# bt_rc_car_remote.net
KiCad netlist of a schematic drawn in EAGLE
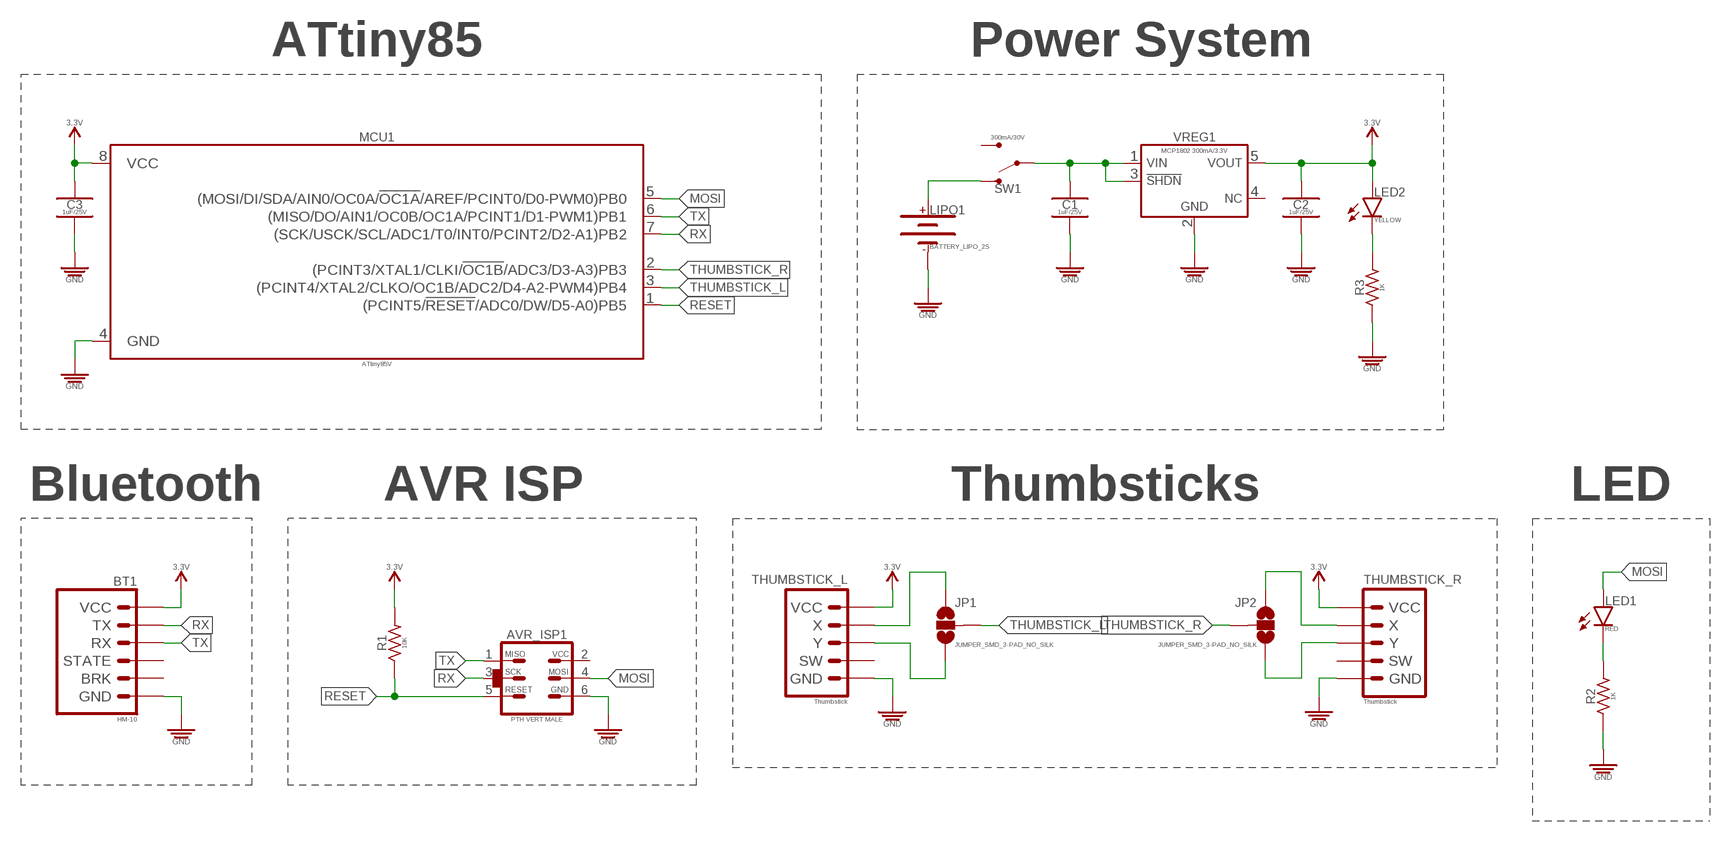
[diagram p0: schematic, sheet 1]

(export (version "E")
  (design (tool "Eeschema 10.0.6"))
  (components
    (comp (ref "AVR_ISP1")
      (value "PTH VERT MALE")
      (footprint "eagle-import:HDRV6W64P254_2X3_762X483X838B_AVR-ISP")
      (fields (field (name "MFR") "Amphenol FCI") (field (name "MPN") "67997-206HLF"))
      (libsource (lib "eagle-import") (part "AVR_SPI_PRG_6_PTH_VERT_MALE_2.54MM"))
    )
    (comp (ref "BT1")
      (value "HM-10")
      (footprint "eagle-import:HDRRAR6W60P254_1X6_1574X850X274B")
      (fields (field (name "MFR") "JNHuaMao Technology Company"))
      (libsource (lib "eagle-import") (part "BLUETOOTH_HM-10_PTH_RA_FEMALE_2.54MM"))
    )
    (comp (ref "C1")
      (value "1uF/25V")
      (footprint "eagle-import:CAPC2012X95_SMD-0805")
      (fields (field (name "MFR") "KEMET") (field (name "MPN") "C0805C105K3RACTU"))
      (libsource (lib "eagle-import") (part "1UF_CER_SMD-0805_25V-10%"))
    )
    (comp (ref "C2")
      (value "1uF/25V")
      (footprint "eagle-import:CAPC2012X95_SMD-0805")
      (fields (field (name "MFR") "KEMET") (field (name "MPN") "C0805C105K3RACTU"))
      (libsource (lib "eagle-import") (part "1UF_CER_SMD-0805_25V-10%"))
    )
    (comp (ref "C3")
      (value "1uF/25V")
      (footprint "eagle-import:CAPC2012X95_SMD-0805")
      (fields (field (name "MFR") "KEMET") (field (name "MPN") "C0805C105K3RACTU"))
      (libsource (lib "eagle-import") (part "1UF_CER_SMD-0805_25V-10%"))
    )
    (comp (ref "JP1")
      (value "JUMPER_SMD_3-PAD_NO_SILK")
      (footprint "eagle-import:SMT-JUMPER_3_NO_SILK")
      (libsource (lib "eagle-import") (part "JUMPER_SMD_3-PAD_NO_SILK"))
    )
    (comp (ref "JP2")
      (value "JUMPER_SMD_3-PAD_NO_SILK")
      (footprint "eagle-import:SMT-JUMPER_3_NO_SILK")
      (libsource (lib "eagle-import") (part "JUMPER_SMD_3-PAD_NO_SILK"))
    )
    (comp (ref "LED1")
      (value "RED")
      (footprint "eagle-import:LEDC2012X120_LED-0805")
      (fields (field (name "MFR") "Lite-On Inc.") (field (name "MPN") "LTST-C170KRKT"))
      (libsource (lib "eagle-import") (part "LED_SMD-0805_DISCRETE_RED"))
    )
    (comp (ref "LED2")
      (value "YELLOW")
      (footprint "eagle-import:LEDC2012X120_LED-0805")
      (fields (field (name "MFR") "Lite-On Inc.") (field (name "MPN") "LTST-C170KSKT"))
      (libsource (lib "eagle-import") (part "LED_SMD-0805_DISCRETE_YELLOW"))
    )
    (comp (ref "LIPO1")
      (value "BATTERY_LIPO_2S")
      (footprint "eagle-import:DUAL_PTH_PADS")
      (libsource (lib "eagle-import") (part "BATTERY_LIPO_2S"))
    )
    (comp (ref "MCU1")
      (value "ATtiny85V")
      (footprint "eagle-import:SOIC127P798X216-8")
      (fields (field (name "MFR") "Microchip Technology") (field (name "MPN") "ATTINY85V-10SU"))
      (libsource (lib "eagle-import") (part "ATTINY-X5_SO-8_ATTINY-85V"))
    )
    (comp (ref "R1")
      (value "10K")
      (footprint "eagle-import:RESC2012X60_SMD-0805")
      (fields (field (name "MFR") "Yageo") (field (name "MPN") "RC0805JR-0710KL"))
      (libsource (lib "eagle-import") (part "10KΩ_SMD-0805_1/8W-5%"))
    )
    (comp (ref "R2")
      (value "1K")
      (footprint "eagle-import:RESC2012X60_SMD-0805")
      (fields (field (name "MFR") "Yageo") (field (name "MPN") "RC0805JR-071KL"))
      (libsource (lib "eagle-import") (part "1KΩ_SMD-0805_1/8W-5%"))
    )
    (comp (ref "R3")
      (value "1K")
      (footprint "eagle-import:RESC2012X60_SMD-0805")
      (fields (field (name "MFR") "Yageo") (field (name "MPN") "RC0805JR-071KL"))
      (libsource (lib "eagle-import") (part "1KΩ_SMD-0805_1/8W-5%"))
    )
    (comp (ref "SW1")
      (value "300mA/30V")
      (footprint "eagle-import:SW_SLIDE_SPDT_VERT_8.6L-4.3W")
      (fields (field (name "MFR") "C&K") (field (name "MPN") "SS-12D07-VG 4 NS GA PA"))
      (libsource (lib "eagle-import") (part "SWITCH_SPDT_PTH_VERT_300MA-30V_8.6L-4.3W"))
    )
    (comp (ref "THUMBSTICK_L")
      (value "Thumbstick")
      (footprint "eagle-import:HDRRAR5W60P254_1X5_1320X850X274B")
      (fields (field (name "MFR") "WGCD"))
      (libsource (lib "eagle-import") (part "THUMBSTICK-2AXIS_BREAKOUT_PTH_RA_FEMALE_2.54MM"))
    )
    (comp (ref "THUMBSTICK_R")
      (value "Thumbstick")
      (footprint "eagle-import:HDRRAR5W60P254_1X5_1320X850X274B")
      (fields (field (name "MFR") "WGCD"))
      (libsource (lib "eagle-import") (part "THUMBSTICK-2AXIS_BREAKOUT_PTH_RA_FEMALE_2.54MM"))
    )
    (comp (ref "VREG1")
      (value "MCP1802 300mA/3.3V")
      (footprint "eagle-import:SOT95P280X145-5")
      (fields (field (name "MFR") "Microchip Technology") (field (name "MPN") "MCP1802T-3302I/OT"))
      (libsource (lib "eagle-import") (part "MCP18XX_MCP1802-330_300MA-3.3V"))
    )
  )
  (nets
    (net (code "1") (name "3.3V") (class "Default")
      (node (ref "BT1") (pin "VCC") (pinfunction "VCC_VCC") (pintype "passive"))
      (node (ref "C2") (pin "1") (pinfunction "1_1") (pintype "passive"))
      (node (ref "C3") (pin "1") (pinfunction "1_1") (pintype "passive"))
      (node (ref "LED2") (pin "A") (pinfunction "A_A") (pintype "passive"))
      (node (ref "MCU1") (pin "8") (pinfunction "VCC_8") (pintype "power_in"))
      (node (ref "R1") (pin "2") (pinfunction "2_2") (pintype "passive"))
      (node (ref "THUMBSTICK_L") (pin "VCC") (pinfunction "VCC_VCC") (pintype "passive"))
      (node (ref "THUMBSTICK_R") (pin "VCC") (pinfunction "VCC_VCC") (pintype "passive"))
      (node (ref "VREG1") (pin "5") (pinfunction "VOUT_5") (pintype "passive"))
    )
    (net (code "2") (name "GND") (class "Default")
      (node (ref "AVR_ISP1") (pin "GND") (pinfunction "GND_GND") (pintype "power_in"))
      (node (ref "BT1") (pin "GND") (pinfunction "GND_GND") (pintype "passive"))
      (node (ref "C1") (pin "2") (pinfunction "2_2") (pintype "passive"))
      (node (ref "C2") (pin "2") (pinfunction "2_2") (pintype "passive"))
      (node (ref "C3") (pin "2") (pinfunction "2_2") (pintype "passive"))
      (node (ref "LIPO1") (pin "-") (pinfunction "-_-") (pintype "power_in"))
      (node (ref "MCU1") (pin "4") (pinfunction "GND_4") (pintype "power_in"))
      (node (ref "R2") (pin "1") (pinfunction "1_1") (pintype "passive"))
      (node (ref "R3") (pin "1") (pinfunction "1_1") (pintype "passive"))
      (node (ref "THUMBSTICK_L") (pin "GND") (pinfunction "GND_GND") (pintype "passive"))
      (node (ref "THUMBSTICK_R") (pin "GND") (pinfunction "GND_GND") (pintype "passive"))
      (node (ref "VREG1") (pin "2") (pinfunction "GND_2") (pintype "passive"))
    )
    (net (code "3") (name "MOSI") (class "Default")
      (node (ref "AVR_ISP1") (pin "MOSI") (pinfunction "MOSI_MOSI") (pintype "bidirectional"))
      (node (ref "LED1") (pin "A") (pinfunction "A_A") (pintype "passive"))
      (node (ref "MCU1") (pin "5") (pinfunction "(MOSI/DI/SDA/AIN0/OC0A/~{OC1A}/AREF/PCINT0/D0-PWM0)PB0_5") (pintype "bidirectional"))
    )
    (net (code "4") (name "Net-(JP1-Pad1)") (class "Default")
      (node (ref "JP1") (pin "1") (pinfunction "1_1") (pintype "passive"))
      (node (ref "THUMBSTICK_L") (pin "X") (pinfunction "X_X") (pintype "output"))
    )
    (net (code "5") (name "Net-(JP1-Pad3)") (class "Default")
      (node (ref "JP1") (pin "3") (pinfunction "3_3") (pintype "passive"))
      (node (ref "THUMBSTICK_L") (pin "Y") (pinfunction "Y_Y") (pintype "output"))
    )
    (net (code "6") (name "Net-(JP2-Pad1)") (class "Default")
      (node (ref "JP2") (pin "1") (pinfunction "1_1") (pintype "passive"))
      (node (ref "THUMBSTICK_R") (pin "X") (pinfunction "X_X") (pintype "output"))
    )
    (net (code "7") (name "Net-(JP2-Pad3)") (class "Default")
      (node (ref "JP2") (pin "3") (pinfunction "3_3") (pintype "passive"))
      (node (ref "THUMBSTICK_R") (pin "Y") (pinfunction "Y_Y") (pintype "output"))
    )
    (net (code "8") (name "Net-(LED1-PadK)") (class "Default")
      (node (ref "LED1") (pin "K") (pinfunction "K_K") (pintype "passive"))
      (node (ref "R2") (pin "2") (pinfunction "2_2") (pintype "passive"))
    )
    (net (code "9") (name "Net-(LED2-PadK)") (class "Default")
      (node (ref "LED2") (pin "K") (pinfunction "K_K") (pintype "passive"))
      (node (ref "R3") (pin "2") (pinfunction "2_2") (pintype "passive"))
    )
    (net (code "10") (name "Net-(LIPO1-Pad+)") (class "Default")
      (node (ref "LIPO1") (pin "+") (pinfunction "+_+") (pintype "power_in"))
      (node (ref "SW1") (pin "S1") (pinfunction "S1_S1") (pintype "passive"))
    )
    (net (code "11") (name "Net-(VREG1-VIN)") (class "Default")
      (node (ref "C1") (pin "1") (pinfunction "1_1") (pintype "passive"))
      (node (ref "SW1") (pin "P") (pinfunction "P_P") (pintype "passive"))
      (node (ref "VREG1") (pin "1") (pinfunction "VIN_1") (pintype "passive"))
      (node (ref "VREG1") (pin "3") (pinfunction "~{SHDN}_3") (pintype "passive"))
    )
    (net (code "12") (name "RESET") (class "Default")
      (node (ref "AVR_ISP1") (pin "RESET") (pinfunction "RESET_RESET") (pintype "bidirectional"))
      (node (ref "MCU1") (pin "1") (pinfunction "(PCINT5/~{RESET}/ADC0/DW/D5-A0)PB5_1") (pintype "bidirectional"))
      (node (ref "R1") (pin "1") (pinfunction "1_1") (pintype "passive"))
    )
    (net (code "13") (name "RX") (class "Default")
      (node (ref "AVR_ISP1") (pin "SCK") (pinfunction "SCK_SCK") (pintype "bidirectional"))
      (node (ref "BT1") (pin "TX") (pinfunction "TX_TX") (pintype "output"))
      (node (ref "MCU1") (pin "7") (pinfunction "(SCK/USCK/SCL/ADC1/T0/INT0/PCINT2/D2-A1)PB2_7") (pintype "bidirectional"))
    )
    (net (code "14") (name "THUMBSTICK_L") (class "Default")
      (node (ref "JP1") (pin "2") (pinfunction "2_2") (pintype "passive"))
      (node (ref "MCU1") (pin "3") (pinfunction "(PCINT4/XTAL2/CLKO/OC1B/ADC2/D4-A2-PWM4)PB4_3") (pintype "bidirectional"))
    )
    (net (code "15") (name "THUMBSTICK_R") (class "Default")
      (node (ref "JP2") (pin "2") (pinfunction "2_2") (pintype "passive"))
      (node (ref "MCU1") (pin "2") (pinfunction "(PCINT3/XTAL1/CLKI/~{OC1B}/ADC3/D3-A3)PB3_2") (pintype "bidirectional"))
    )
    (net (code "16") (name "TX") (class "Default")
      (node (ref "AVR_ISP1") (pin "MISO") (pinfunction "MISO_MISO") (pintype "bidirectional"))
      (node (ref "BT1") (pin "RX") (pinfunction "RX_RX") (pintype "input"))
      (node (ref "MCU1") (pin "6") (pinfunction "(MISO/DO/AIN1/OC0B/OC1A/PCINT1/D1-PWM1)PB1_6") (pintype "bidirectional"))
    )
    (net (code "17") (name "unconnected-(AVR_ISP1-PadVCC)") (class "Default")
      (node (ref "AVR_ISP1") (pin "VCC") (pinfunction "VCC_VCC") (pintype "no_connect"))
    )
    (net (code "18") (name "unconnected-(BT1-PadBRK)") (class "Default")
      (node (ref "BT1") (pin "BRK") (pinfunction "BRK_BRK") (pintype "no_connect"))
    )
    (net (code "19") (name "unconnected-(BT1-PadSTATE)") (class "Default")
      (node (ref "BT1") (pin "STATE") (pinfunction "STATE_STATE") (pintype "no_connect"))
    )
    (net (code "20") (name "unconnected-(SW1-PadS2)") (class "Default")
      (node (ref "SW1") (pin "S2") (pinfunction "S2_S2") (pintype "passive"))
    )
    (net (code "21") (name "unconnected-(THUMBSTICK_L-PadSW)") (class "Default")
      (node (ref "THUMBSTICK_L") (pin "SW") (pinfunction "SW_SW") (pintype "bidirectional"))
    )
    (net (code "22") (name "unconnected-(THUMBSTICK_R-PadSW)") (class "Default")
      (node (ref "THUMBSTICK_R") (pin "SW") (pinfunction "SW_SW") (pintype "bidirectional"))
    )
    (net (code "23") (name "unconnected-(VREG1-NC-Pad4)") (class "Default")
      (node (ref "VREG1") (pin "4") (pinfunction "NC_4") (pintype "passive"))
    )
  )
)
